# PB1_LTC2400_DAQ.net
KiCad netlist of a schematic drawn in EAGLE
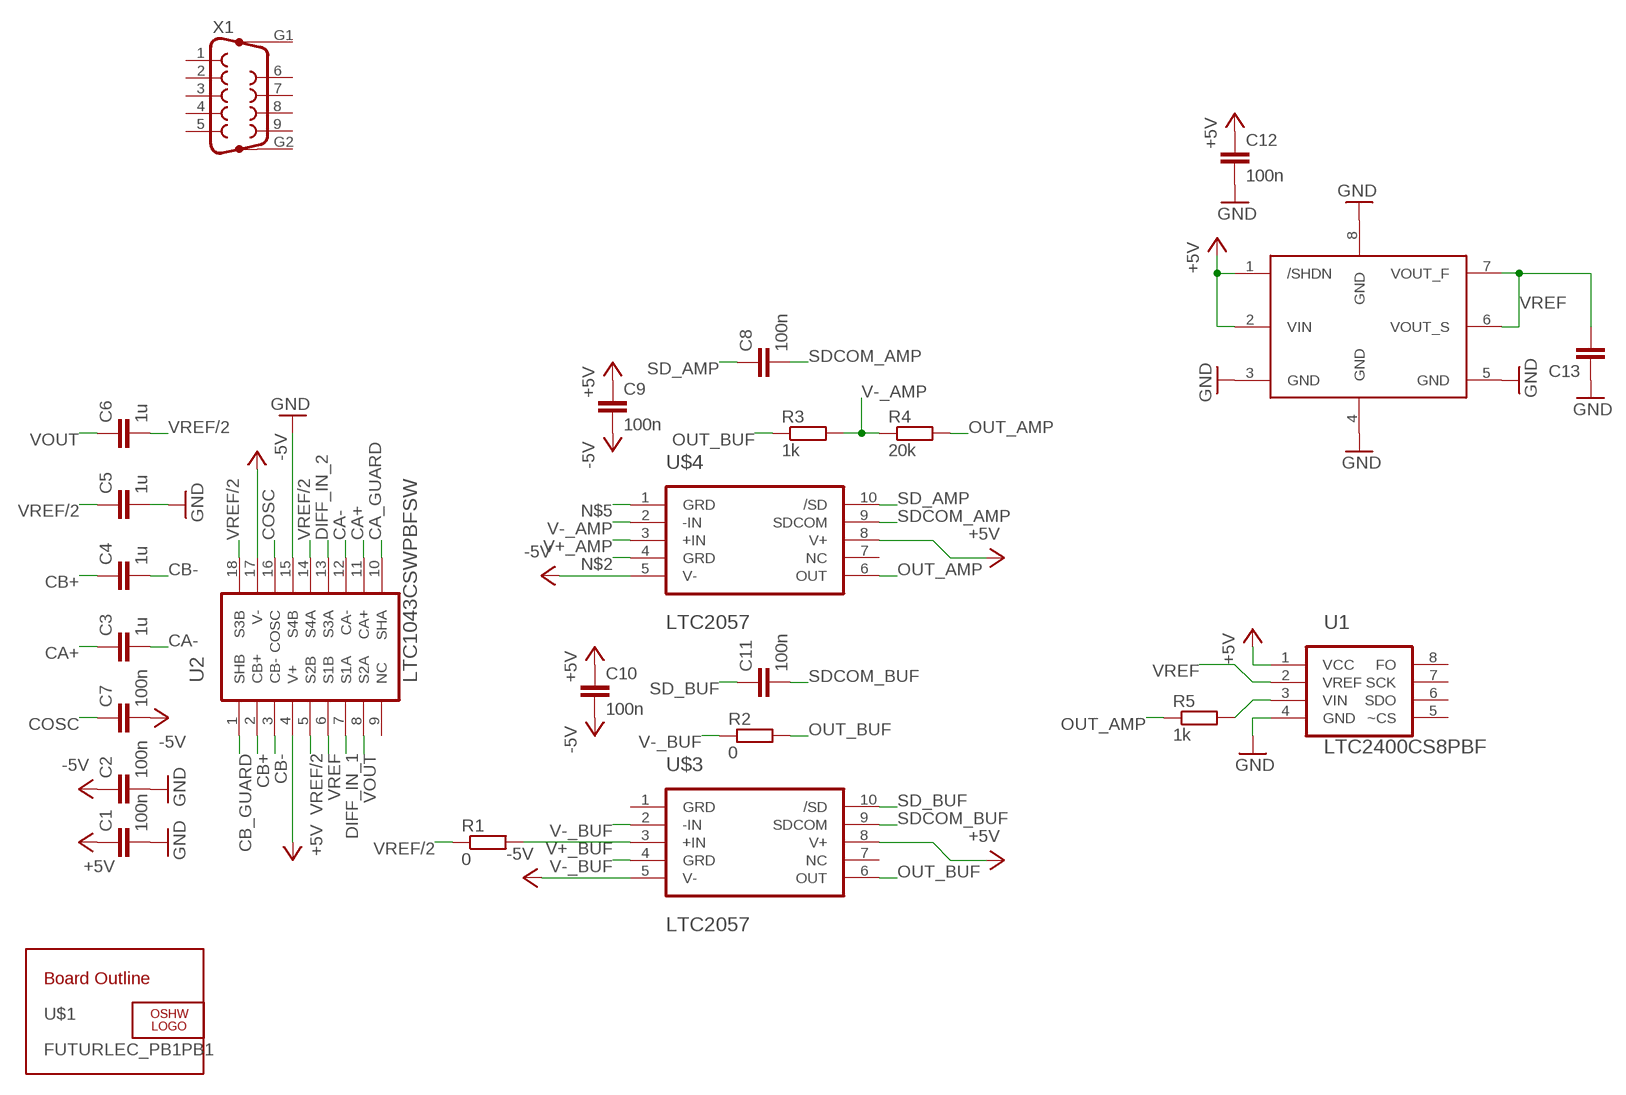
[diagram p0: schematic, sheet 1]

(export (version "E")
  (design (tool "Eeschema 10.0.6"))
  (components
    (comp (ref "C1")
      (value "100n")
      (footprint "eagle-import:C1812K")
      (libsource (lib "eagle-import") (part "C-EUC1812K"))
    )
    (comp (ref "C2")
      (value "100n")
      (footprint "eagle-import:C1812K")
      (libsource (lib "eagle-import") (part "C-EUC1812K"))
    )
    (comp (ref "C3")
      (value "1u")
      (footprint "eagle-import:C2220K")
      (libsource (lib "eagle-import") (part "C-EUC2220K"))
    )
    (comp (ref "C4")
      (value "1u")
      (footprint "eagle-import:C2220K")
      (libsource (lib "eagle-import") (part "C-EUC2220K"))
    )
    (comp (ref "C5")
      (value "1u")
      (footprint "eagle-import:C2220K")
      (libsource (lib "eagle-import") (part "C-EUC2220K"))
    )
    (comp (ref "C6")
      (value "1u")
      (footprint "eagle-import:C2220K")
      (libsource (lib "eagle-import") (part "C-EUC2220K"))
    )
    (comp (ref "C7")
      (value "100n")
      (footprint "eagle-import:C1812K")
      (libsource (lib "eagle-import") (part "C-EUC1812K"))
    )
    (comp (ref "C8")
      (value "100n")
      (footprint "eagle-import:C0603")
      (libsource (lib "eagle-import") (part "C-EUC0603"))
    )
    (comp (ref "C9")
      (value "100n")
      (footprint "eagle-import:C1812K")
      (libsource (lib "eagle-import") (part "C-EUC1812K"))
    )
    (comp (ref "C10")
      (value "100n")
      (footprint "eagle-import:C1812K")
      (libsource (lib "eagle-import") (part "C-EUC1812K"))
    )
    (comp (ref "C11")
      (value "100n")
      (footprint "eagle-import:C0603")
      (libsource (lib "eagle-import") (part "C-EUC0603"))
    )
    (comp (ref "C12")
      (value "100n")
      (footprint "eagle-import:C1812K")
      (libsource (lib "eagle-import") (part "C-EUC1812K"))
    )
    (comp (ref "C13")
      (value "C-EU075-063X106")
      (footprint "eagle-import:C075-063X106")
      (libsource (lib "eagle-import") (part "C-EU075-063X106"))
    )
    (comp (ref "LOGO1")
      (value "OSHW_LOGO_8MILX0200-NT")
      (footprint "eagle-import:OSHW_8X200_NOTEXT")
      (libsource (lib "eagle-import") (part "OSHW_LOGO_8MILX0200-NT"))
    )
    (comp (ref "R1")
      (value "0")
      (footprint "eagle-import:R0805")
      (libsource (lib "eagle-import") (part "R-EU_R0805"))
    )
    (comp (ref "R2")
      (value "0")
      (footprint "eagle-import:R0805")
      (libsource (lib "eagle-import") (part "R-EU_R0805"))
    )
    (comp (ref "R3")
      (value "1k")
      (footprint "eagle-import:R0805")
      (libsource (lib "eagle-import") (part "R-EU_R0805"))
    )
    (comp (ref "R4")
      (value "20k")
      (footprint "eagle-import:R0805")
      (libsource (lib "eagle-import") (part "R-EU_R0805"))
    )
    (comp (ref "R5")
      (value "1k")
      (footprint "eagle-import:R0805")
      (libsource (lib "eagle-import") (part "R-EU_R0805"))
    )
    (comp (ref "U$1")
      (value "FUTURLEC_PB1PB1")
      (footprint "eagle-import:FUTURLEC_PB1")
      (libsource (lib "eagle-import") (part "FUTURLEC_PB1PB1"))
    )
    (comp (ref "U$2")
      (value "LTC6655LS8_ELONG")
      (footprint "eagle-import:LS8_ELONG")
      (libsource (lib "eagle-import") (part "LTC6655LS8_ELONG"))
    )
    (comp (ref "U$3")
      (value "LTC2057")
      (footprint "eagle-import:MS-MSOP10")
      (libsource (lib "eagle-import") (part "LTC2057"))
    )
    (comp (ref "U$4")
      (value "LTC2057")
      (footprint "eagle-import:MS-MSOP10")
      (libsource (lib "eagle-import") (part "LTC2057"))
    )
    (comp (ref "U1")
      (value "LTC2400CS8PBF")
      (footprint "eagle-import:SOIC127P600X175-8N")
      (fields (field (name "MPN") "LTC2400CS8#PBF"))
      (libsource (lib "eagle-import") (part "LTC2400CS8PBF"))
    )
    (comp (ref "U2")
      (value "LTC1043CSWPBFSW")
      (footprint "eagle-import:SOIC127P1032X264-18N")
      (fields (field (name "MPN") "LTC1043CSW#PBF"))
      (libsource (lib "eagle-import") (part "LTC1043CSWPBFSW"))
    )
    (comp (ref "X1")
      (value "F09VP")
      (footprint "eagle-import:F09VP")
      (libsource (lib "eagle-import") (part "F09VP"))
    )
  )
  (nets
    (net (code "1") (name "+5V") (class "Default")
      (node (ref "C1") (pin "1") (pinfunction "1_1") (pintype "passive"))
      (node (ref "C10") (pin "1") (pinfunction "1_1") (pintype "passive"))
      (node (ref "C12") (pin "1") (pinfunction "1_1") (pintype "passive"))
      (node (ref "C9") (pin "1") (pinfunction "1_1") (pintype "passive"))
      (node (ref "U$2") (pin "1") (pinfunction "/SHDN_1") (pintype "input"))
      (node (ref "U$2") (pin "2") (pinfunction "VIN_2") (pintype "input"))
      (node (ref "U$3") (pin "8") (pinfunction "V+_8") (pintype "bidirectional"))
      (node (ref "U$4") (pin "8") (pinfunction "V+_8") (pintype "bidirectional"))
      (node (ref "U1") (pin "1") (pinfunction "VCC_1") (pintype "power_in"))
      (node (ref "U2") (pin "4") (pinfunction "V+_4") (pintype "power_in"))
    )
    (net (code "2") (name "-5V") (class "Default")
      (node (ref "C10") (pin "2") (pinfunction "2_2") (pintype "passive"))
      (node (ref "C2") (pin "1") (pinfunction "1_1") (pintype "passive"))
      (node (ref "C7") (pin "2") (pinfunction "2_2") (pintype "passive"))
      (node (ref "C9") (pin "2") (pinfunction "2_2") (pintype "passive"))
      (node (ref "U$3") (pin "5") (pinfunction "V-_5") (pintype "bidirectional"))
      (node (ref "U$4") (pin "5") (pinfunction "V-_5") (pintype "bidirectional"))
      (node (ref "U2") (pin "17") (pinfunction "V-_17") (pintype "power_in"))
    )
    (net (code "3") (name "/CA+") (class "Default")
      (node (ref "C3") (pin "1") (pinfunction "1_1") (pintype "passive"))
      (node (ref "U2") (pin "11") (pinfunction "CA+_11") (pintype "passive"))
    )
    (net (code "4") (name "/CA-") (class "Default")
      (node (ref "C3") (pin "2") (pinfunction "2_2") (pintype "passive"))
      (node (ref "U2") (pin "12") (pinfunction "CA-_12") (pintype "passive"))
    )
    (net (code "5") (name "/CA_GUARD") (class "Default")
      (node (ref "U2") (pin "10") (pinfunction "SHA_10") (pintype "passive"))
    )
    (net (code "6") (name "/CB+") (class "Default")
      (node (ref "C4") (pin "1") (pinfunction "1_1") (pintype "passive"))
      (node (ref "U2") (pin "2") (pinfunction "CB+_2") (pintype "passive"))
    )
    (net (code "7") (name "/CB-") (class "Default")
      (node (ref "C4") (pin "2") (pinfunction "2_2") (pintype "passive"))
      (node (ref "U2") (pin "3") (pinfunction "CB-_3") (pintype "passive"))
    )
    (net (code "8") (name "/CB_GUARD") (class "Default")
      (node (ref "U2") (pin "1") (pinfunction "SHB_1") (pintype "passive"))
    )
    (net (code "9") (name "/COSC") (class "Default")
      (node (ref "C7") (pin "1") (pinfunction "1_1") (pintype "passive"))
      (node (ref "U2") (pin "16") (pinfunction "COSC_16") (pintype "passive"))
    )
    (net (code "10") (name "/DIFF_IN_1") (class "Default")
      (node (ref "U2") (pin "7") (pinfunction "S1A_7") (pintype "passive"))
    )
    (net (code "11") (name "/DIFF_IN_2") (class "Default")
      (node (ref "U2") (pin "13") (pinfunction "S3A_13") (pintype "passive"))
    )
    (net (code "12") (name "/N$2") (class "Default")
      (node (ref "U$4") (pin "4") (pinfunction "GRD_4") (pintype "bidirectional"))
    )
    (net (code "13") (name "/N$5") (class "Default")
      (node (ref "U$4") (pin "1") (pinfunction "GRD_1") (pintype "bidirectional"))
    )
    (net (code "14") (name "/OUT_AMP") (class "Default")
      (node (ref "R4") (pin "2") (pinfunction "2_2") (pintype "passive"))
      (node (ref "R5") (pin "1") (pinfunction "1_1") (pintype "passive"))
      (node (ref "U$4") (pin "6") (pinfunction "OUT_6") (pintype "bidirectional"))
    )
    (net (code "15") (name "/OUT_BUF") (class "Default")
      (node (ref "R2") (pin "2") (pinfunction "2_2") (pintype "passive"))
      (node (ref "R3") (pin "1") (pinfunction "1_1") (pintype "passive"))
      (node (ref "U$3") (pin "6") (pinfunction "OUT_6") (pintype "bidirectional"))
    )
    (net (code "16") (name "/SDCOM_AMP") (class "Default")
      (node (ref "C8") (pin "2") (pinfunction "2_2") (pintype "passive"))
      (node (ref "U$4") (pin "9") (pinfunction "SDCOM_9") (pintype "bidirectional"))
    )
    (net (code "17") (name "/SDCOM_BUF") (class "Default")
      (node (ref "C11") (pin "2") (pinfunction "2_2") (pintype "passive"))
      (node (ref "U$3") (pin "9") (pinfunction "SDCOM_9") (pintype "bidirectional"))
    )
    (net (code "18") (name "/SD_AMP") (class "Default")
      (node (ref "C8") (pin "1") (pinfunction "1_1") (pintype "passive"))
      (node (ref "U$4") (pin "10") (pinfunction "/SD_10") (pintype "bidirectional"))
    )
    (net (code "19") (name "/SD_BUF") (class "Default")
      (node (ref "C11") (pin "1") (pinfunction "1_1") (pintype "passive"))
      (node (ref "U$3") (pin "10") (pinfunction "/SD_10") (pintype "bidirectional"))
    )
    (net (code "20") (name "/V+_AMP") (class "Default")
      (node (ref "U$4") (pin "3") (pinfunction "+IN_3") (pintype "bidirectional"))
    )
    (net (code "21") (name "/V+_BUF") (class "Default")
      (node (ref "R1") (pin "2") (pinfunction "2_2") (pintype "passive"))
      (node (ref "U$3") (pin "3") (pinfunction "+IN_3") (pintype "bidirectional"))
    )
    (net (code "22") (name "/V-_AMP") (class "Default")
      (node (ref "R3") (pin "2") (pinfunction "2_2") (pintype "passive"))
      (node (ref "R4") (pin "1") (pinfunction "1_1") (pintype "passive"))
      (node (ref "U$4") (pin "2") (pinfunction "-IN_2") (pintype "bidirectional"))
    )
    (net (code "23") (name "/V-_BUF") (class "Default")
      (node (ref "R2") (pin "1") (pinfunction "1_1") (pintype "passive"))
      (node (ref "U$3") (pin "2") (pinfunction "-IN_2") (pintype "bidirectional"))
      (node (ref "U$3") (pin "4") (pinfunction "GRD_4") (pintype "bidirectional"))
    )
    (net (code "24") (name "/VOUT") (class "Default")
      (node (ref "C6") (pin "1") (pinfunction "1_1") (pintype "passive"))
      (node (ref "U2") (pin "8") (pinfunction "S2A_8") (pintype "passive"))
    )
    (net (code "25") (name "/VREF") (class "Default")
      (node (ref "C13") (pin "2") (pinfunction "2_2") (pintype "passive"))
      (node (ref "U$2") (pin "6") (pinfunction "VOUT_S_6") (pintype "input"))
      (node (ref "U$2") (pin "7") (pinfunction "VOUT_F_7") (pintype "input"))
      (node (ref "U1") (pin "2") (pinfunction "VREF_2") (pintype "input"))
      (node (ref "U2") (pin "6") (pinfunction "S1B_6") (pintype "passive"))
    )
    (net (code "26") (name "/VREF{slash}2") (class "Default")
      (node (ref "C5") (pin "1") (pinfunction "1_1") (pintype "passive"))
      (node (ref "C6") (pin "2") (pinfunction "2_2") (pintype "passive"))
      (node (ref "R1") (pin "1") (pinfunction "1_1") (pintype "passive"))
      (node (ref "U2") (pin "14") (pinfunction "S4A_14") (pintype "passive"))
      (node (ref "U2") (pin "18") (pinfunction "S3B_18") (pintype "passive"))
      (node (ref "U2") (pin "5") (pinfunction "S2B_5") (pintype "passive"))
    )
    (net (code "27") (name "GND") (class "Default")
      (node (ref "C1") (pin "2") (pinfunction "2_2") (pintype "passive"))
      (node (ref "C12") (pin "2") (pinfunction "2_2") (pintype "passive"))
      (node (ref "C13") (pin "1") (pinfunction "1_1") (pintype "passive"))
      (node (ref "C2") (pin "2") (pinfunction "2_2") (pintype "passive"))
      (node (ref "C5") (pin "2") (pinfunction "2_2") (pintype "passive"))
      (node (ref "U$2") (pin "3") (pinfunction "GND_3") (pintype "input"))
      (node (ref "U$2") (pin "4") (pinfunction "GND_4") (pintype "input"))
      (node (ref "U$2") (pin "5") (pinfunction "GND_5") (pintype "input"))
      (node (ref "U$2") (pin "8") (pinfunction "GND_8") (pintype "input"))
      (node (ref "U1") (pin "4") (pinfunction "GND_4") (pintype "passive"))
      (node (ref "U2") (pin "15") (pinfunction "S4B_15") (pintype "passive"))
    )
    (net (code "28") (name "Net-(U1-VIN)") (class "Default")
      (node (ref "R5") (pin "2") (pinfunction "2_2") (pintype "passive"))
      (node (ref "U1") (pin "3") (pinfunction "VIN_3") (pintype "input"))
    )
    (net (code "29") (name "unconnected-(U$3-GRD-Pad1)") (class "Default")
      (node (ref "U$3") (pin "1") (pinfunction "GRD_1") (pintype "bidirectional"))
    )
    (net (code "30") (name "unconnected-(U$3-NC-Pad7)") (class "Default")
      (node (ref "U$3") (pin "7") (pinfunction "NC_7") (pintype "bidirectional"))
    )
    (net (code "31") (name "unconnected-(U$4-NC-Pad7)") (class "Default")
      (node (ref "U$4") (pin "7") (pinfunction "NC_7") (pintype "bidirectional"))
    )
    (net (code "32") (name "unconnected-(U1-FO-Pad8)") (class "Default")
      (node (ref "U1") (pin "8") (pinfunction "FO_8") (pintype "input"))
    )
    (net (code "33") (name "unconnected-(U1-SCK-Pad7)") (class "Default")
      (node (ref "U1") (pin "7") (pinfunction "SCK_7") (pintype "input"))
    )
    (net (code "34") (name "unconnected-(U1-SDO-Pad6)") (class "Default")
      (node (ref "U1") (pin "6") (pinfunction "SDO_6") (pintype "output"))
    )
    (net (code "35") (name "unconnected-(U1-~{CS}-Pad5)") (class "Default")
      (node (ref "U1") (pin "5") (pinfunction "~{CS}_5") (pintype "input"))
    )
    (net (code "36") (name "unconnected-(U2-NC-Pad9)") (class "Default")
      (node (ref "U2") (pin "9") (pinfunction "NC_9") (pintype "no_connect"))
    )
    (net (code "37") (name "unconnected-(X1-Pad1)") (class "Default")
      (node (ref "X1") (pin "1") (pinfunction "1_1") (pintype "passive"))
    )
    (net (code "38") (name "unconnected-(X1-Pad2)") (class "Default")
      (node (ref "X1") (pin "2") (pinfunction "2_2") (pintype "passive"))
    )
    (net (code "39") (name "unconnected-(X1-Pad3)") (class "Default")
      (node (ref "X1") (pin "3") (pinfunction "3_3") (pintype "passive"))
    )
    (net (code "40") (name "unconnected-(X1-Pad4)") (class "Default")
      (node (ref "X1") (pin "4") (pinfunction "4_4") (pintype "passive"))
    )
    (net (code "41") (name "unconnected-(X1-Pad5)") (class "Default")
      (node (ref "X1") (pin "5") (pinfunction "5_5") (pintype "passive"))
    )
    (net (code "42") (name "unconnected-(X1-Pad6)") (class "Default")
      (node (ref "X1") (pin "6") (pinfunction "6_6") (pintype "passive"))
    )
    (net (code "43") (name "unconnected-(X1-Pad7)") (class "Default")
      (node (ref "X1") (pin "7") (pinfunction "7_7") (pintype "passive"))
    )
    (net (code "44") (name "unconnected-(X1-Pad8)") (class "Default")
      (node (ref "X1") (pin "8") (pinfunction "8_8") (pintype "passive"))
    )
    (net (code "45") (name "unconnected-(X1-Pad9)") (class "Default")
      (node (ref "X1") (pin "9") (pinfunction "9_9") (pintype "passive"))
    )
    (net (code "46") (name "unconnected-(X1-PadG1)") (class "Default")
      (node (ref "X1") (pin "G1") (pinfunction "G1_G1") (pintype "passive"))
    )
    (net (code "47") (name "unconnected-(X1-PadG2)") (class "Default")
      (node (ref "X1") (pin "G2") (pinfunction "G2_G2") (pintype "passive"))
    )
  )
)
